# portalgate.net
KiCad netlist of a schematic drawn in EAGLE
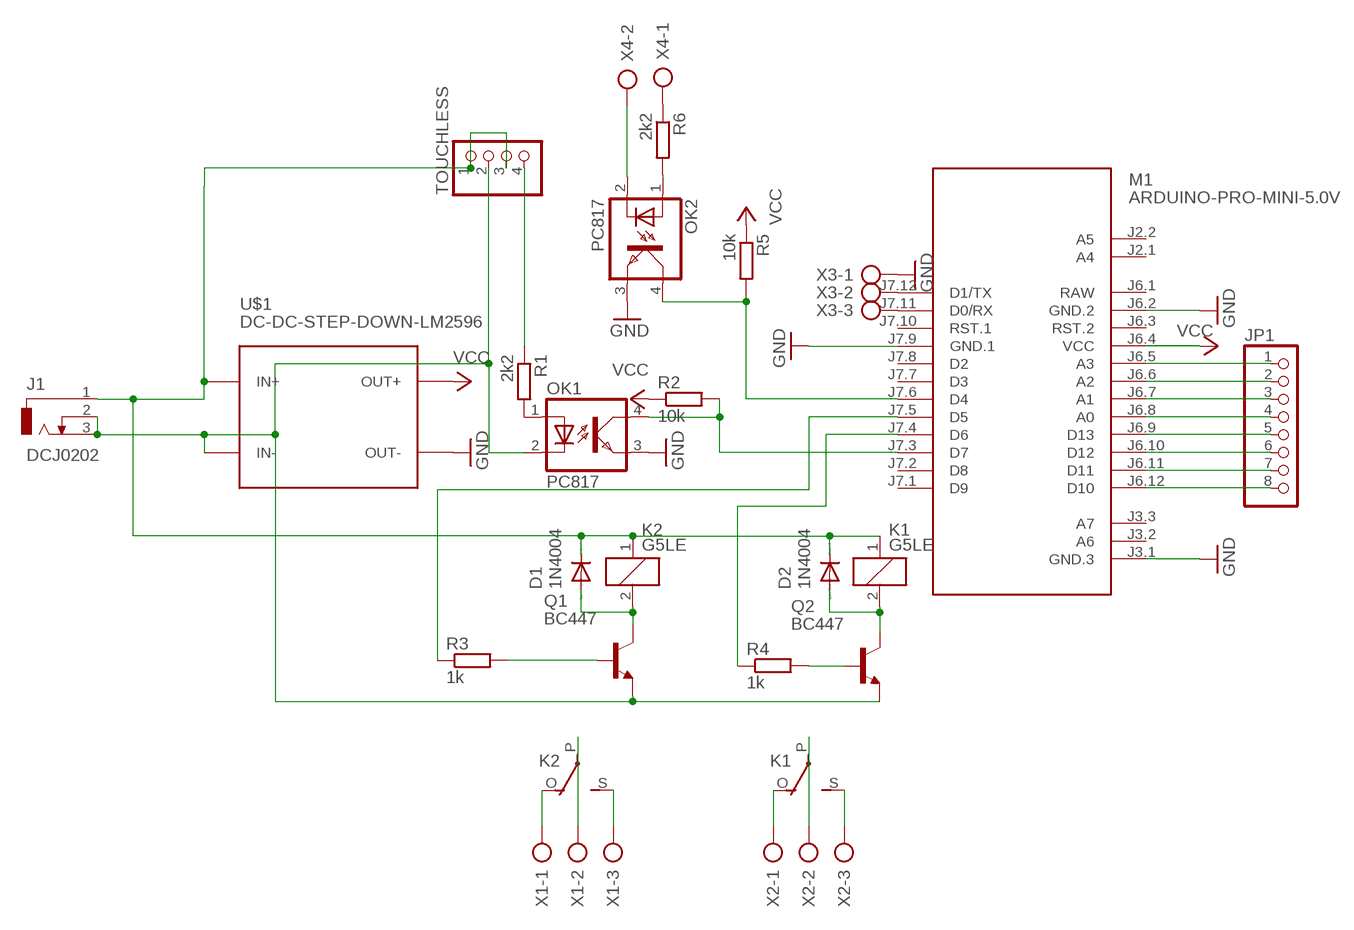
[diagram p0: schematic, sheet 1]

(export (version "E")
  (design (tool "Eeschema 10.0.6"))
  (components
    (comp (ref "D1")
      (value "1N4004")
      (footprint "eagle-import:DO41-10")
      (libsource (lib "eagle-import") (part "1N4004"))
    )
    (comp (ref "D2")
      (value "1N4004")
      (footprint "eagle-import:DO41-10")
      (libsource (lib "eagle-import") (part "1N4004"))
    )
    (comp (ref "J1")
      (value "DCJ0202")
      (footprint "eagle-import:DCJ0202")
      (libsource (lib "eagle-import") (part "DCJ0202"))
    )
    (comp (ref "JP1")
      (value "PINHD-1X8")
      (footprint "eagle-import:1X08")
      (libsource (lib "eagle-import") (part "PINHD-1X8"))
    )
    (comp (ref "K1")
      (value "G5LE")
      (footprint "eagle-import:G5LE")
      (libsource (lib "eagle-import") (part "G5LE"))
    )
    (comp (ref "K2")
      (value "G5LE")
      (footprint "eagle-import:G5LE")
      (libsource (lib "eagle-import") (part "G5LE"))
    )
    (comp (ref "M1")
      (value "ARDUINO-PRO-MINI-5.0V")
      (footprint "eagle-import:ARDUINO-PRO-MINI")
      (libsource (lib "eagle-import") (part "ARDUINO-PRO-MINI-5.0V"))
    )
    (comp (ref "OK1")
      (value "PC817")
      (footprint "eagle-import:DIL04")
      (fields (field (name "MPN") "PC817X4J000F"))
      (libsource (lib "eagle-import") (part "PC817"))
    )
    (comp (ref "OK2")
      (value "PC817")
      (footprint "eagle-import:DIL04")
      (fields (field (name "MPN") "PC817X4J000F"))
      (libsource (lib "eagle-import") (part "PC817"))
    )
    (comp (ref "Q1")
      (value "BC447")
      (footprint "eagle-import:TO92-EBC")
      (libsource (lib "eagle-import") (part "BC447"))
    )
    (comp (ref "Q2")
      (value "BC447")
      (footprint "eagle-import:TO92-EBC")
      (libsource (lib "eagle-import") (part "BC447"))
    )
    (comp (ref "R1")
      (value "2k2")
      (footprint "eagle-import:0204_7")
      (libsource (lib "eagle-import") (part "R-EU_0204/7"))
    )
    (comp (ref "R2")
      (value "10k")
      (footprint "eagle-import:0204_7")
      (libsource (lib "eagle-import") (part "R-EU_0204/7"))
    )
    (comp (ref "R3")
      (value "1k")
      (footprint "eagle-import:0204_7")
      (libsource (lib "eagle-import") (part "R-EU_0204/7"))
    )
    (comp (ref "R4")
      (value "1k")
      (footprint "eagle-import:0204_7")
      (libsource (lib "eagle-import") (part "R-EU_0204/7"))
    )
    (comp (ref "R5")
      (value "10k")
      (footprint "eagle-import:0204_7")
      (libsource (lib "eagle-import") (part "R-EU_0204/7"))
    )
    (comp (ref "R6")
      (value "2k2")
      (footprint "eagle-import:0204_7")
      (libsource (lib "eagle-import") (part "R-EU_0204/7"))
    )
    (comp (ref "TOUCHLESS")
      (value "PINHD-1X4")
      (footprint "eagle-import:1X04")
      (libsource (lib "eagle-import") (part "PINHD-1X4"))
    )
    (comp (ref "U$1")
      (value "DC-DC-STEP-DOWN-LM2596")
      (footprint "eagle-import:DC-DC-STEP-DOWN-LM2596")
      (libsource (lib "eagle-import") (part "DC-DC-STEP-DOWN-LM2596"))
    )
    (comp (ref "X1")
      (value "AK300/3")
      (footprint "eagle-import:AK300_3")
      (libsource (lib "eagle-import") (part "AK300/3"))
    )
    (comp (ref "X2")
      (value "AK300/3")
      (footprint "eagle-import:AK300_3")
      (libsource (lib "eagle-import") (part "AK300/3"))
    )
    (comp (ref "X3")
      (value "AK300/3")
      (footprint "eagle-import:AK300_3")
      (libsource (lib "eagle-import") (part "AK300/3"))
    )
    (comp (ref "X4")
      (value "AK300/2")
      (footprint "eagle-import:AK300_2")
      (libsource (lib "eagle-import") (part "AK300/2"))
    )
  )
  (nets
    (net (code "1") (name "/RAW") (class "Default")
      (node (ref "M1") (pin "J6.1") (pinfunction "RAW_J6.1") (pintype "power_in"))
    )
    (net (code "2") (name "GND") (class "Default")
      (node (ref "M1") (pin "J3.1") (pinfunction "GND.3_J3.1") (pintype "bidirectional"))
      (node (ref "M1") (pin "J6.2") (pinfunction "GND.2_J6.2") (pintype "power_in"))
      (node (ref "M1") (pin "J7.9") (pinfunction "GND.1_J7.9") (pintype "power_in"))
      (node (ref "OK1") (pin "3") (pinfunction "EMIT_3") (pintype "passive"))
      (node (ref "OK2") (pin "3") (pinfunction "EMIT_3") (pintype "passive"))
      (node (ref "U$1") (pin "OUT-") (pinfunction "OUT-_OUT-") (pintype "bidirectional"))
      (node (ref "X3") (pin "1") (pinfunction "KL_1") (pintype "passive"))
    )
    (net (code "3") (name "Net-(D1-PadA)") (class "Default")
      (node (ref "D1") (pin "A") (pinfunction "A_A") (pintype "passive"))
      (node (ref "K2") (pin "2") (pinfunction "2_2") (pintype "passive"))
      (node (ref "Q1") (pin "C") (pinfunction "C_C") (pintype "passive"))
    )
    (net (code "4") (name "Net-(D1-PadC)") (class "Default")
      (node (ref "D1") (pin "C") (pinfunction "C_C") (pintype "passive"))
      (node (ref "D2") (pin "C") (pinfunction "C_C") (pintype "passive"))
      (node (ref "J1") (pin "1") (pinfunction "1_1") (pintype "passive"))
      (node (ref "K1") (pin "1") (pinfunction "1_1") (pintype "passive"))
      (node (ref "K2") (pin "1") (pinfunction "1_1") (pintype "passive"))
      (node (ref "TOUCHLESS") (pin "1") (pinfunction "1_1") (pintype "passive"))
      (node (ref "TOUCHLESS") (pin "3") (pinfunction "3_3") (pintype "passive"))
      (node (ref "U$1") (pin "IN+") (pinfunction "IN+_IN+") (pintype "bidirectional"))
    )
    (net (code "5") (name "Net-(D2-PadA)") (class "Default")
      (node (ref "D2") (pin "A") (pinfunction "A_A") (pintype "passive"))
      (node (ref "K1") (pin "2") (pinfunction "2_2") (pintype "passive"))
      (node (ref "Q2") (pin "C") (pinfunction "C_C") (pintype "passive"))
    )
    (net (code "6") (name "Net-(M1-A0)") (class "Default")
      (node (ref "JP1") (pin "4") (pinfunction "4_4") (pintype "passive"))
      (node (ref "M1") (pin "J6.8") (pinfunction "A0_J6.8") (pintype "bidirectional"))
    )
    (net (code "7") (name "Net-(M1-A1)") (class "Default")
      (node (ref "JP1") (pin "3") (pinfunction "3_3") (pintype "passive"))
      (node (ref "M1") (pin "J6.7") (pinfunction "A1_J6.7") (pintype "bidirectional"))
    )
    (net (code "8") (name "Net-(M1-A2)") (class "Default")
      (node (ref "JP1") (pin "2") (pinfunction "2_2") (pintype "passive"))
      (node (ref "M1") (pin "J6.6") (pinfunction "A2_J6.6") (pintype "bidirectional"))
    )
    (net (code "9") (name "Net-(M1-A3)") (class "Default")
      (node (ref "JP1") (pin "1") (pinfunction "1_1") (pintype "passive"))
      (node (ref "M1") (pin "J6.5") (pinfunction "A3_J6.5") (pintype "bidirectional"))
    )
    (net (code "10") (name "Net-(M1-D0{slash}RX)") (class "Default")
      (node (ref "M1") (pin "J7.11") (pinfunction "D0/RX_J7.11") (pintype "bidirectional"))
      (node (ref "X3") (pin "3") (pinfunction "KL_3") (pintype "passive"))
    )
    (net (code "11") (name "Net-(M1-D1{slash}TX)") (class "Default")
      (node (ref "M1") (pin "J7.12") (pinfunction "D1/TX_J7.12") (pintype "bidirectional"))
      (node (ref "X3") (pin "2") (pinfunction "KL_2") (pintype "passive"))
    )
    (net (code "12") (name "Net-(M1-D4)") (class "Default")
      (node (ref "M1") (pin "J7.6") (pinfunction "D4_J7.6") (pintype "bidirectional"))
      (node (ref "OK2") (pin "4") (pinfunction "COL_4") (pintype "passive"))
      (node (ref "R5") (pin "2") (pinfunction "2_2") (pintype "passive"))
    )
    (net (code "13") (name "Net-(M1-D5)") (class "Default")
      (node (ref "M1") (pin "J7.5") (pinfunction "D5_J7.5") (pintype "bidirectional"))
      (node (ref "R3") (pin "1") (pinfunction "1_1") (pintype "passive"))
    )
    (net (code "14") (name "Net-(M1-D6)") (class "Default")
      (node (ref "M1") (pin "J7.4") (pinfunction "D6_J7.4") (pintype "bidirectional"))
      (node (ref "R4") (pin "1") (pinfunction "1_1") (pintype "passive"))
    )
    (net (code "15") (name "Net-(M1-D7)") (class "Default")
      (node (ref "M1") (pin "J7.3") (pinfunction "D7_J7.3") (pintype "bidirectional"))
      (node (ref "OK1") (pin "4") (pinfunction "COL_4") (pintype "passive"))
      (node (ref "R2") (pin "2") (pinfunction "2_2") (pintype "passive"))
    )
    (net (code "16") (name "Net-(M1-D10)") (class "Default")
      (node (ref "JP1") (pin "8") (pinfunction "8_8") (pintype "passive"))
      (node (ref "M1") (pin "J6.12") (pinfunction "D10_J6.12") (pintype "bidirectional"))
    )
    (net (code "17") (name "Net-(M1-D11)") (class "Default")
      (node (ref "JP1") (pin "7") (pinfunction "7_7") (pintype "passive"))
      (node (ref "M1") (pin "J6.11") (pinfunction "D11_J6.11") (pintype "bidirectional"))
    )
    (net (code "18") (name "Net-(M1-D12)") (class "Default")
      (node (ref "JP1") (pin "6") (pinfunction "6_6") (pintype "passive"))
      (node (ref "M1") (pin "J6.10") (pinfunction "D12_J6.10") (pintype "bidirectional"))
    )
    (net (code "19") (name "Net-(M1-D13)") (class "Default")
      (node (ref "JP1") (pin "5") (pinfunction "5_5") (pintype "passive"))
      (node (ref "M1") (pin "J6.9") (pinfunction "D13_J6.9") (pintype "bidirectional"))
    )
    (net (code "20") (name "Net-(OK1-A)") (class "Default")
      (node (ref "OK1") (pin "1") (pinfunction "A_1") (pintype "passive"))
      (node (ref "R1") (pin "2") (pinfunction "2_2") (pintype "passive"))
    )
    (net (code "21") (name "Net-(OK1-C)") (class "Default")
      (node (ref "J1") (pin "2") (pinfunction "2_2") (pintype "passive"))
      (node (ref "J1") (pin "3") (pinfunction "3_3") (pintype "passive"))
      (node (ref "OK1") (pin "2") (pinfunction "C_2") (pintype "passive"))
      (node (ref "Q1") (pin "E") (pinfunction "E_E") (pintype "passive"))
      (node (ref "Q2") (pin "E") (pinfunction "E_E") (pintype "passive"))
      (node (ref "TOUCHLESS") (pin "2") (pinfunction "2_2") (pintype "passive"))
      (node (ref "U$1") (pin "IN-") (pinfunction "IN-_IN-") (pintype "bidirectional"))
    )
    (net (code "22") (name "Net-(OK2-A)") (class "Default")
      (node (ref "OK2") (pin "1") (pinfunction "A_1") (pintype "passive"))
      (node (ref "R6") (pin "2") (pinfunction "2_2") (pintype "passive"))
    )
    (net (code "23") (name "Net-(OK2-C)") (class "Default")
      (node (ref "OK2") (pin "2") (pinfunction "C_2") (pintype "passive"))
      (node (ref "X4") (pin "2") (pinfunction "KL_2") (pintype "passive"))
    )
    (net (code "24") (name "Net-(Q1-PadB)") (class "Default")
      (node (ref "Q1") (pin "B") (pinfunction "B_B") (pintype "passive"))
      (node (ref "R3") (pin "2") (pinfunction "2_2") (pintype "passive"))
    )
    (net (code "25") (name "Net-(Q2-PadB)") (class "Default")
      (node (ref "Q2") (pin "B") (pinfunction "B_B") (pintype "passive"))
      (node (ref "R4") (pin "2") (pinfunction "2_2") (pintype "passive"))
    )
    (net (code "26") (name "Net-(R1-Pad1)") (class "Default")
      (node (ref "R1") (pin "1") (pinfunction "1_1") (pintype "passive"))
      (node (ref "TOUCHLESS") (pin "4") (pinfunction "4_4") (pintype "passive"))
    )
    (net (code "27") (name "Net-(X1A-KL)") (class "Default")
      (node (ref "K2") (pin "O") (pinfunction "O_O") (pintype "passive"))
      (node (ref "X1") (pin "1") (pinfunction "KL_1") (pintype "passive"))
    )
    (net (code "28") (name "Net-(X1B-KL)") (class "Default")
      (node (ref "K2") (pin "P") (pinfunction "P_P") (pintype "passive"))
      (node (ref "X1") (pin "2") (pinfunction "KL_2") (pintype "passive"))
    )
    (net (code "29") (name "Net-(X1C-KL)") (class "Default")
      (node (ref "K2") (pin "S") (pinfunction "S_S") (pintype "passive"))
      (node (ref "X1") (pin "3") (pinfunction "KL_3") (pintype "passive"))
    )
    (net (code "30") (name "Net-(X2A-KL)") (class "Default")
      (node (ref "K1") (pin "O") (pinfunction "O_O") (pintype "passive"))
      (node (ref "X2") (pin "1") (pinfunction "KL_1") (pintype "passive"))
    )
    (net (code "31") (name "Net-(X2B-KL)") (class "Default")
      (node (ref "K1") (pin "P") (pinfunction "P_P") (pintype "passive"))
      (node (ref "X2") (pin "2") (pinfunction "KL_2") (pintype "passive"))
    )
    (net (code "32") (name "Net-(X2C-KL)") (class "Default")
      (node (ref "K1") (pin "S") (pinfunction "S_S") (pintype "passive"))
      (node (ref "X2") (pin "3") (pinfunction "KL_3") (pintype "passive"))
    )
    (net (code "33") (name "Net-(X4A-KL)") (class "Default")
      (node (ref "R6") (pin "1") (pinfunction "1_1") (pintype "passive"))
      (node (ref "X4") (pin "1") (pinfunction "KL_1") (pintype "passive"))
    )
    (net (code "34") (name "VCC") (class "Default")
      (node (ref "M1") (pin "J6.4") (pinfunction "VCC_J6.4") (pintype "power_in"))
      (node (ref "R2") (pin "1") (pinfunction "1_1") (pintype "passive"))
      (node (ref "R5") (pin "1") (pinfunction "1_1") (pintype "passive"))
      (node (ref "U$1") (pin "OUT+") (pinfunction "OUT+_OUT+") (pintype "bidirectional"))
    )
    (net (code "35") (name "unconnected-(M1-A4-PadJ2.1)") (class "Default")
      (node (ref "M1") (pin "J2.1") (pinfunction "A4_J2.1") (pintype "bidirectional"))
    )
    (net (code "36") (name "unconnected-(M1-A5-PadJ2.2)") (class "Default")
      (node (ref "M1") (pin "J2.2") (pinfunction "A5_J2.2") (pintype "bidirectional"))
    )
    (net (code "37") (name "unconnected-(M1-A6-PadJ3.2)") (class "Default")
      (node (ref "M1") (pin "J3.2") (pinfunction "A6_J3.2") (pintype "bidirectional"))
    )
    (net (code "38") (name "unconnected-(M1-A7-PadJ3.3)") (class "Default")
      (node (ref "M1") (pin "J3.3") (pinfunction "A7_J3.3") (pintype "bidirectional"))
    )
    (net (code "39") (name "unconnected-(M1-D2-PadJ7.8)") (class "Default")
      (node (ref "M1") (pin "J7.8") (pinfunction "D2_J7.8") (pintype "bidirectional"))
    )
    (net (code "40") (name "unconnected-(M1-D3-PadJ7.7)") (class "Default")
      (node (ref "M1") (pin "J7.7") (pinfunction "D3_J7.7") (pintype "bidirectional"))
    )
    (net (code "41") (name "unconnected-(M1-D8-PadJ7.2)") (class "Default")
      (node (ref "M1") (pin "J7.2") (pinfunction "D8_J7.2") (pintype "bidirectional"))
    )
    (net (code "42") (name "unconnected-(M1-D9-PadJ7.1)") (class "Default")
      (node (ref "M1") (pin "J7.1") (pinfunction "D9_J7.1") (pintype "bidirectional"))
    )
    (net (code "43") (name "unconnected-(M1-RST.1-PadJ7.10)") (class "Default")
      (node (ref "M1") (pin "J7.10") (pinfunction "RST.1_J7.10") (pintype "bidirectional"))
    )
    (net (code "44") (name "unconnected-(M1-RST.2-PadJ6.3)") (class "Default")
      (node (ref "M1") (pin "J6.3") (pinfunction "RST.2_J6.3") (pintype "bidirectional"))
    )
  )
)
